# Relay_IO.net
KiCad netlist of a schematic drawn in Altium Designer
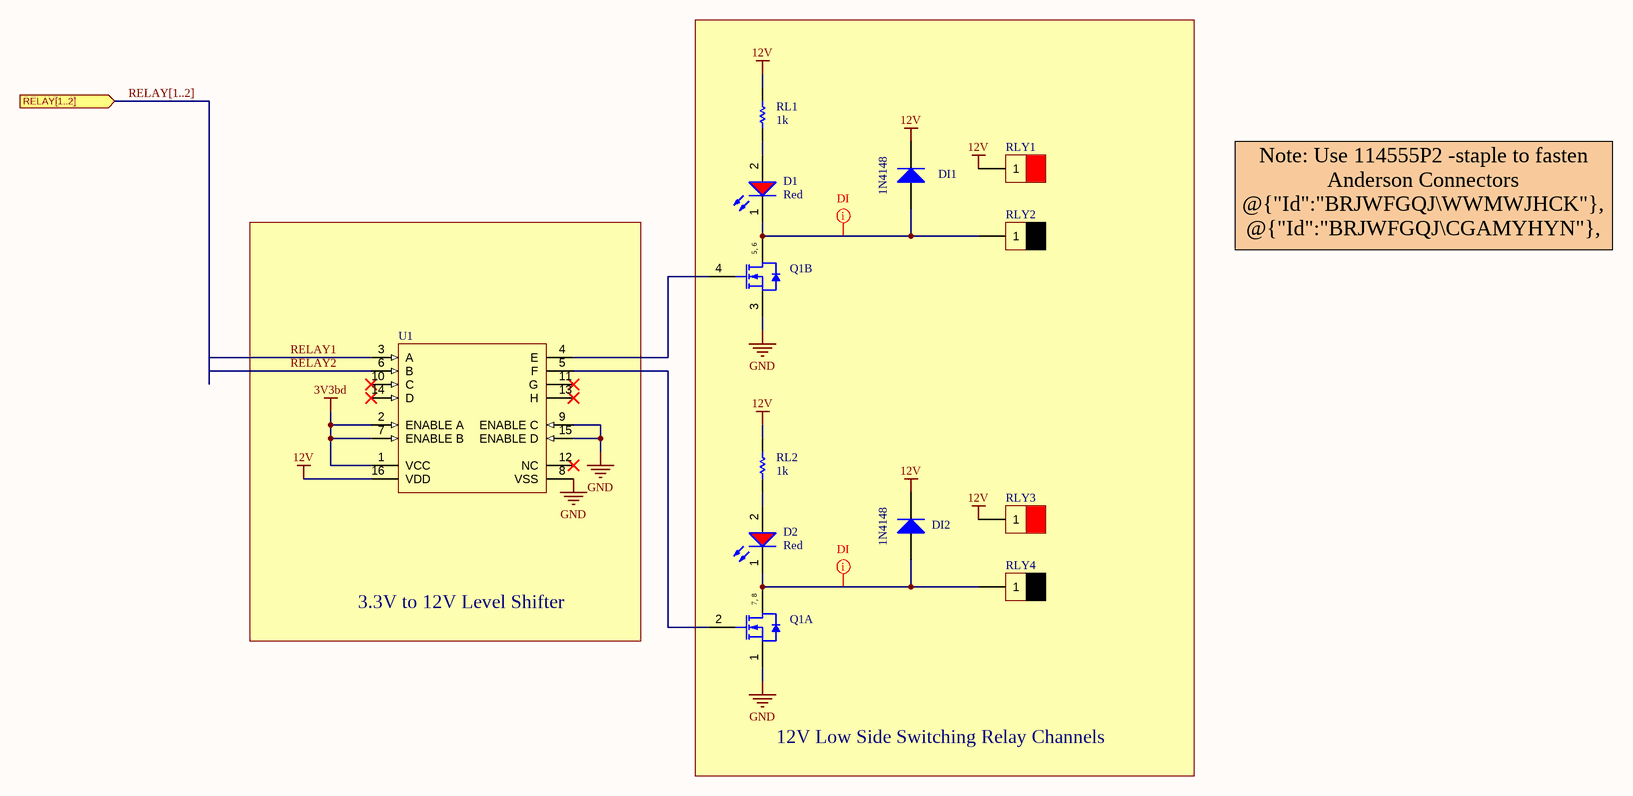
[diagram p0:  Relay_IO.SchDoc]

(export (version "E")
  (design (tool "Eeschema 10.0.6"))
  (components
    (comp (ref "D1")
      (value "LED Red")
      (footprint "0603_A")
      (description "Single Color LED, Red, Water Clear, 1.1mm")
      (fields
        (field (name "COLOR") "Red")
        (field (name "MANUFACTURER") "Wurth Electronics")
        (field (name "MANUFACTURER PART NUMBER") "150060RS75000")
      )
      (libsource (lib "MHH -  Altium Advanced Course A365 01") (part "CMP-007-00000-1"))
    )
    (comp (ref "D2")
      (value "LED Red")
      (footprint "0603_A")
      (description "Single Color LED, Red, Water Clear, 1.1mm")
      (fields
        (field (name "COLOR") "Red")
        (field (name "MANUFACTURER") "Wurth Electronics")
        (field (name "MANUFACTURER PART NUMBER") "150060RS75000")
      )
      (libsource (lib "MHH -  Altium Advanced Course A365 01") (part "CMP-007-00000-1"))
    )
    (comp (ref "DI1")
      (value "1N4148")
      (footprint "DO-41")
      (description "Rectifier Diode, 1 Phase, 1 Element, 1A, 100V V(RRM), Silicon, DO-41")
      (fields
        (field (name "MANUFACTURER") "ON Semiconductor")
        (field (name "MANUFACTURER PART NUMBER") "MUR110RLG")
      )
      (libsource (lib "MHH -  Altium Advanced Course A365 01") (part "CMP-00241-2"))
    )
    (comp (ref "DI2")
      (value "1N4148")
      (footprint "DO-41")
      (description "Rectifier Diode, 1 Phase, 1 Element, 1A, 100V V(RRM), Silicon, DO-41")
      (fields
        (field (name "MANUFACTURER") "ON Semiconductor")
        (field (name "MANUFACTURER PART NUMBER") "MUR110RLG")
      )
      (libsource (lib "MHH -  Altium Advanced Course A365 01") (part "CMP-00241-2"))
    )
    (comp (ref "Q1")
      (value "NTHD4508NT1")
      (footprint "ONSC-CHIPFET-8-1206A-03_S2_V")
      (description "Small Signal Field-Effect Transistor")
      (fields
        (field (name "MANUFACTURER") "ON Semiconductor")
        (field (name "MANUFACTURER PART NUMBER") "NTHD4508NT1G")
      )
      (libsource (lib "MHH -  Altium Advanced Course A365 01") (part "CMP-013-00000-2"))
    )
    (comp (ref "RL1")
      (value "Res1K_0805")
      (footprint "0805_L")
      (fields
        (field (name "MANUFACTURER") "Panasonic")
        (field (name "MANUFACTURER PART NUMBER") "ERJ-6GEYJ102V")
        (field (name "RESISTANCE (OHMS)") "1k")
        (field (name "TOLERANCE") "5%")
        (field (name "SOURCE") "WCT.SchLib")
      )
      (libsource (lib "MHH -  Altium Advanced Course A365 01") (part "CMP-00124-1"))
    )
    (comp (ref "RL2")
      (value "Res1K_0805")
      (footprint "0805_L")
      (fields
        (field (name "MANUFACTURER") "Panasonic")
        (field (name "MANUFACTURER PART NUMBER") "ERJ-6GEYJ102V")
        (field (name "RESISTANCE (OHMS)") "1k")
        (field (name "TOLERANCE") "5%")
        (field (name "SOURCE") "WCT.SchLib")
      )
      (libsource (lib "MHH -  Altium Advanced Course A365 01") (part "CMP-00124-1"))
    )
    (comp (ref "RLY1")
      (value "Anderson RED 1Pin")
      (footprint "Anderson_RED_RHT_BOT")
      (description "Anderson-1Pin RED_PCB_RHT")
      (fields
        (field (name "MANUFACTURER") "Anderson Power")
        (field (name "MANUFACTURER PART NUMBER") "1377G2")
      )
      (libsource (lib "MHH -  Altium Advanced Course A365 01") (part "Anderson RED 1Pin"))
    )
    (comp (ref "RLY2")
      (value "Anderson Black 1Pin")
      (footprint "Anderson_BLK_RHT_BOT")
      (description "Anderson-1Pin BLK_PCB_RHT")
      (fields
        (field (name "MANUFACTURER") "Anderson Power")
        (field (name "MANUFACTURER PART NUMBER") "1327G6")
      )
      (libsource (lib "MHH -  Altium Advanced Course A365 01") (part "Anderson Black 1Pin"))
    )
    (comp (ref "RLY3")
      (value "Anderson RED 1Pin")
      (footprint "Anderson_RED_RHT_BOT")
      (description "Anderson-1Pin RED_PCB_RHT")
      (fields
        (field (name "MANUFACTURER") "Anderson Power")
        (field (name "MANUFACTURER PART NUMBER") "1377G2")
      )
      (libsource (lib "MHH -  Altium Advanced Course A365 01") (part "Anderson RED 1Pin"))
    )
    (comp (ref "RLY4")
      (value "Anderson Black 1Pin")
      (footprint "Anderson_BLK_RHT_BOT")
      (description "Anderson-1Pin BLK_PCB_RHT")
      (fields
        (field (name "MANUFACTURER") "Anderson Power")
        (field (name "MANUFACTURER PART NUMBER") "1327G6")
      )
      (libsource (lib "MHH -  Altium Advanced Course A365 01") (part "Anderson Black 1Pin"))
    )
    (comp (ref "U1")
      (value "CD40109BPWR")
      (footprint "PW0016A_M")
      (fields
        (field (name "MANUFACTURER") "Texas Instruments")
        (field (name "PARTNUMBER") "CD40109BPW")
        (field (name "AVAILABLE PREVIEW IMAGES") "2D")
        (field (name "SOURCE") "WCT.SchLib")
      )
      (libsource (lib "MHH -  Altium Advanced Course A365 01") (part "CD40109BPWR"))
    )
  )
  (nets
    (net (code "1") (name "/RELAY1") (class "Default")
      (node (ref "U1") (pin "3") (pinfunction "A_3") (pintype "input"))
    )
    (net (code "2") (name "/RELAY2") (class "Default")
      (node (ref "U1") (pin "6") (pinfunction "B_6") (pintype "input"))
    )
    (net (code "4") (name "3V3bd") (class "Default")
      (node (ref "U1") (pin "1") (pinfunction "VCC_1") (pintype "power_in"))
      (node (ref "U1") (pin "2") (pinfunction "ENABLE_A_2") (pintype "input"))
      (node (ref "U1") (pin "7") (pinfunction "ENABLE_B_7") (pintype "input"))
    )
    (net (code "5") (name "12V") (class "Default")
      (node (ref "DI1") (pin "2") (pinfunction "K_2") (pintype "passive"))
      (node (ref "DI2") (pin "2") (pinfunction "K_2") (pintype "passive"))
      (node (ref "RL1") (pin "2") (pinfunction "2_2") (pintype "passive"))
      (node (ref "RL2") (pin "2") (pinfunction "2_2") (pintype "passive"))
      (node (ref "RLY1") (pin "1") (pinfunction "1_1") (pintype "passive"))
      (node (ref "RLY3") (pin "1") (pinfunction "1_1") (pintype "passive"))
      (node (ref "U1") (pin "16") (pinfunction "VDD_16") (pintype "power_in"))
    )
    (net (code "6") (name "GND") (class "Default")
      (node (ref "Q1") (pin "1") (pinfunction "S1_1") (pintype "passive"))
      (node (ref "Q1") (pin "3") (pinfunction "S2_3") (pintype "passive"))
      (node (ref "U1") (pin "15") (pinfunction "ENABLE_D_15") (pintype "input"))
      (node (ref "U1") (pin "8") (pinfunction "VSS_8") (pintype "power_in"))
      (node (ref "U1") (pin "9") (pinfunction "ENABLE_C_9") (pintype "input"))
    )
    (net (code "7") (name "Net-(D1-A)") (class "Default")
      (node (ref "D1") (pin "2") (pinfunction "A_2") (pintype "passive"))
      (node (ref "RL1") (pin "1") (pinfunction "1_1") (pintype "passive"))
    )
    (net (code "8") (name "Net-(D1-K)") (class "Default")
      (node (ref "D1") (pin "1") (pinfunction "K_1") (pintype "passive"))
      (node (ref "DI1") (pin "1") (pinfunction "A_1") (pintype "passive"))
      (node (ref "Q1") (pin "5") (pinfunction "D2_5") (pintype "passive"))
      (node (ref "Q1") (pin "6") (pinfunction "D2_6") (pintype "passive"))
      (node (ref "RLY2") (pin "1") (pinfunction "1_1") (pintype "passive"))
    )
    (net (code "9") (name "Net-(D2-A)") (class "Default")
      (node (ref "D2") (pin "2") (pinfunction "A_2") (pintype "passive"))
      (node (ref "RL2") (pin "1") (pinfunction "1_1") (pintype "passive"))
    )
    (net (code "10") (name "Net-(D2-K)") (class "Default")
      (node (ref "D2") (pin "1") (pinfunction "K_1") (pintype "passive"))
      (node (ref "DI2") (pin "1") (pinfunction "A_1") (pintype "passive"))
      (node (ref "Q1") (pin "7") (pinfunction "D1_7") (pintype "passive"))
      (node (ref "Q1") (pin "8") (pinfunction "D1_8") (pintype "passive"))
      (node (ref "RLY4") (pin "1") (pinfunction "1_1") (pintype "passive"))
    )
    (net (code "11") (name "Net-(Q1A-G1)") (class "Default")
      (node (ref "Q1") (pin "2") (pinfunction "G1_2") (pintype "passive"))
      (node (ref "U1") (pin "5") (pinfunction "F_5") (pintype "tri_state"))
    )
    (net (code "12") (name "Net-(Q1B-G2)") (class "Default")
      (node (ref "Q1") (pin "4") (pinfunction "G2_4") (pintype "passive"))
      (node (ref "U1") (pin "4") (pinfunction "E_4") (pintype "tri_state"))
    )
    (net (code "13") (name "unconnected-(U1-C-Pad10)") (class "Default")
      (node (ref "U1") (pin "10") (pinfunction "C_10") (pintype "input+no_connect"))
    )
    (net (code "14") (name "unconnected-(U1-D-Pad14)") (class "Default")
      (node (ref "U1") (pin "14") (pinfunction "D_14") (pintype "input+no_connect"))
    )
    (net (code "15") (name "unconnected-(U1-G-Pad11)") (class "Default")
      (node (ref "U1") (pin "11") (pinfunction "G_11") (pintype "tri_state+no_connect"))
    )
    (net (code "16") (name "unconnected-(U1-H-Pad13)") (class "Default")
      (node (ref "U1") (pin "13") (pinfunction "H_13") (pintype "tri_state+no_connect"))
    )
    (net (code "17") (name "unconnected-(U1-NC-Pad12)") (class "Default")
      (node (ref "U1") (pin "12") (pinfunction "NC_12") (pintype "passive+no_connect"))
    )
  )
)
